# relay.net
KiCad netlist of a schematic drawn in Altium Designer
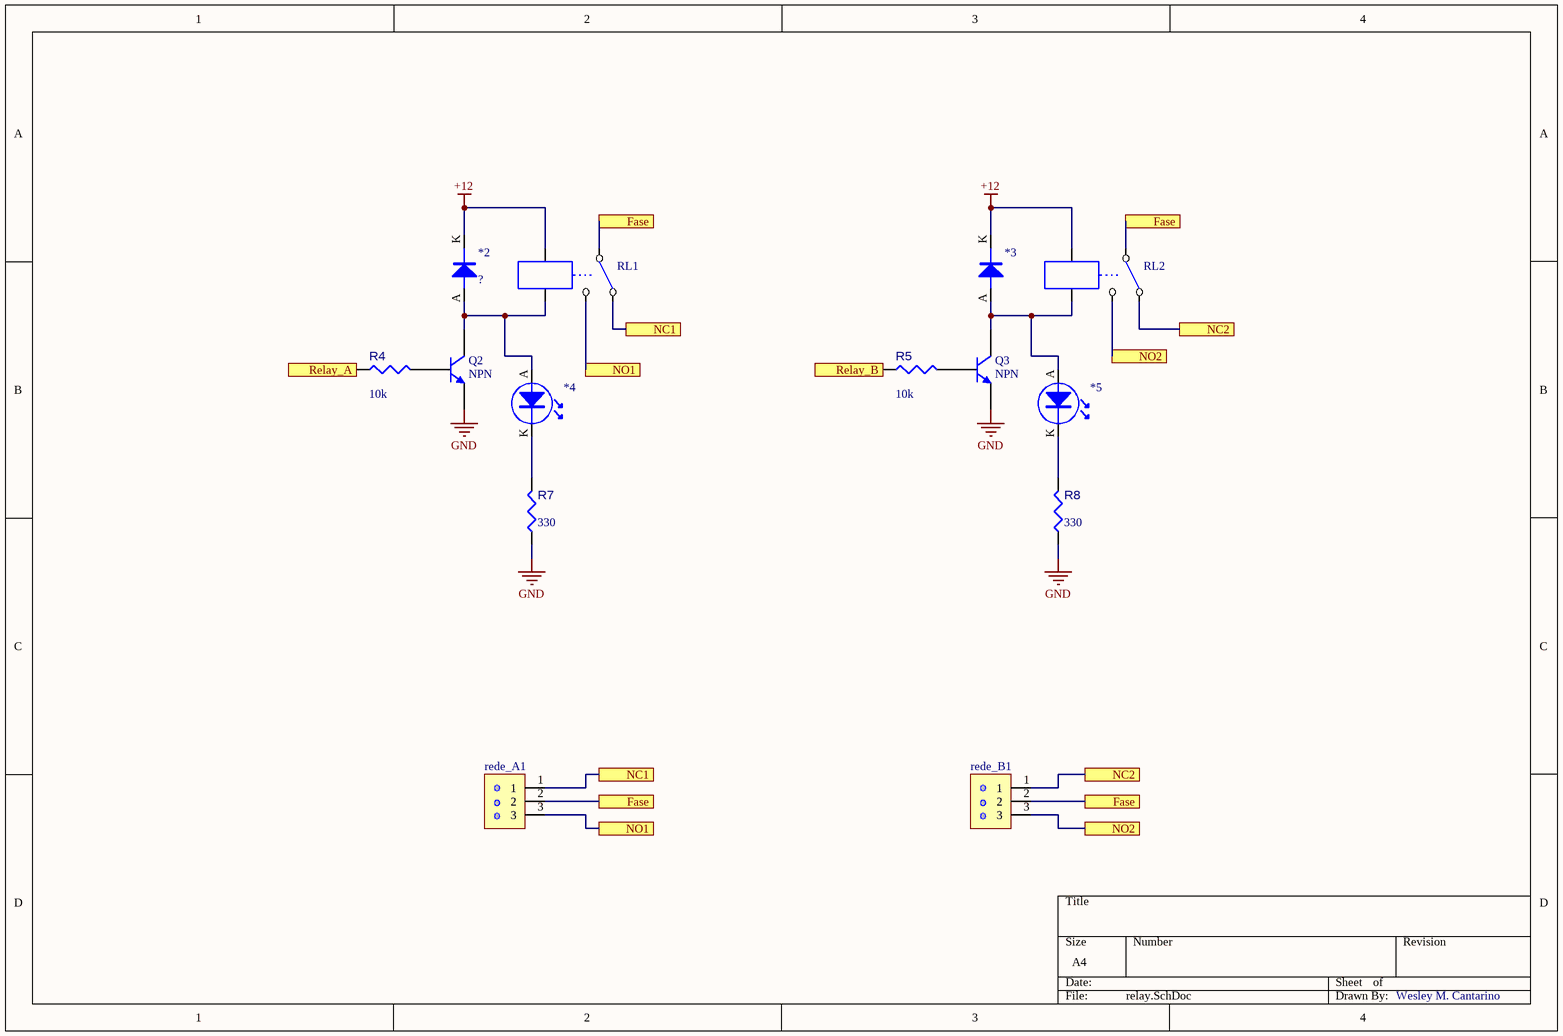
[diagram p0: relay.SchDoc]

(export (version "E")
  (design (tool "Eeschema 10.0.6"))
  (components
    (comp (ref "*2")
      (value "?")
      (footprint "DIO_PTH_DO41")
      (fields (field (name "Comment") "DIO_PTH_1N4007"))
      (libsource (lib "i9Library_Altium") (part "DIO_PTH_1N4007"))
    )
    (comp (ref "*3")
      (value "DIO_PTH_1N4007")
      (footprint "DIO_PTH_DO41")
      (libsource (lib "i9Library_Altium") (part "DIO_PTH_1N4007"))
    )
    (comp (ref "*4")
      (value "LED_AXIAL_5MM")
      (footprint "HEADER_1X2")
      (libsource (lib "i9Library_Altium") (part "LED_AXIAL_5MM"))
    )
    (comp (ref "*5")
      (value "LED_AXIAL_5MM")
      (footprint "HEADER_1X2")
      (libsource (lib "i9Library_Altium") (part "LED_AXIAL_5MM"))
    )
    (comp (ref "Q2")
      (value "NPN")
      (footprint "HEADER_1X3")
      (description "NPN Bipolar Transistor")
      (fields (field (name "PUBLISHER") "Altium Limited"))
      (libsource (lib "Miscellaneous Devices") (part "NPN"))
    )
    (comp (ref "Q3")
      (value "NPN")
      (footprint "HEADER_1X3")
      (description "NPN Bipolar Transistor")
      (fields (field (name "PUBLISHER") "Altium Limited"))
      (libsource (lib "Miscellaneous Devices") (part "NPN"))
    )
    (comp (ref "R4")
      (value "10k")
      (footprint "RES_PTH_7.62MM")
      (description "Pin Through Hole Resistor 7.62mm")
      (libsource (lib "i9Library_Altium") (part "RES_PTH_7.62MM"))
    )
    (comp (ref "R5")
      (value "10k")
      (footprint "RES_PTH_7.62MM")
      (description "Pin Through Hole Resistor 7.62mm")
      (libsource (lib "i9Library_Altium") (part "RES_PTH_7.62MM"))
    )
    (comp (ref "R7")
      (value "330")
      (footprint "RES_PTH_7.62MM")
      (description "Pin Through Hole Resistor 7.62mm")
      (libsource (lib "i9Library_Altium") (part "RES_PTH_7.62MM"))
    )
    (comp (ref "R8")
      (value "330")
      (footprint "RES_PTH_7.62MM")
      (description "Pin Through Hole Resistor 7.62mm")
      (libsource (lib "i9Library_Altium") (part "RES_PTH_7.62MM"))
    )
    (comp (ref "rede_A1")
      (value "?")
      (footprint "CN_KRE_3")
      (description "MKDS_3")
      (libsource (lib "i9Library_Altium") (part "CN_MKDS_3"))
    )
    (comp (ref "rede_B1")
      (value "?")
      (footprint "CN_KRE_3")
      (description "MKDS_3")
      (libsource (lib "i9Library_Altium") (part "CN_MKDS_3"))
    )
    (comp (ref "RL1")
      (value "RELEICR5551")
      (footprint "DIV_RELE_5551")
      (libsource (lib "i9Library_Altium") (part "RELEICR5551"))
    )
    (comp (ref "RL2")
      (value "RELEICR5551")
      (footprint "DIV_RELE_5551")
      (libsource (lib "i9Library_Altium") (part "RELEICR5551"))
    )
  )
  (nets
    (net (code "1") (name "+12") (class "Default")
      (node (ref "*2") (pin "K") (pintype "passive"))
      (node (ref "*3") (pin "K") (pintype "passive"))
      (node (ref "RL1") (pin "4") (pintype "passive"))
      (node (ref "RL2") (pin "4") (pintype "passive"))
    )
    (net (code "2") (name "/Fase") (class "Default")
      (node (ref "RL1") (pin "1") (pintype "passive"))
      (node (ref "RL2") (pin "1") (pintype "passive"))
      (node (ref "rede_A1") (pin "2") (pinfunction "2_2") (pintype "passive"))
      (node (ref "rede_B1") (pin "2") (pinfunction "2_2") (pintype "passive"))
    )
    (net (code "3") (name "/NC1") (class "Default")
      (node (ref "RL1") (pin "2") (pintype "passive"))
      (node (ref "rede_A1") (pin "1") (pinfunction "1_1") (pintype "passive"))
    )
    (net (code "4") (name "/NC2") (class "Default")
      (node (ref "RL2") (pin "2") (pintype "passive"))
      (node (ref "rede_B1") (pin "1") (pinfunction "1_1") (pintype "passive"))
    )
    (net (code "5") (name "/NO1") (class "Default")
      (node (ref "RL1") (pin "3") (pintype "passive"))
      (node (ref "rede_A1") (pin "3") (pinfunction "3_3") (pintype "passive"))
    )
    (net (code "6") (name "/NO2") (class "Default")
      (node (ref "RL2") (pin "3") (pintype "passive"))
      (node (ref "rede_B1") (pin "3") (pinfunction "3_3") (pintype "passive"))
    )
    (net (code "7") (name "/Relay_A") (class "Default")
      (node (ref "R4") (pin "1") (pinfunction "1_1") (pintype "passive"))
    )
    (net (code "8") (name "/Relay_B") (class "Default")
      (node (ref "R5") (pin "1") (pinfunction "1_1") (pintype "passive"))
    )
    (net (code "9") (name "GND") (class "Default")
      (node (ref "Q2") (pin "3") (pinfunction "E_3") (pintype "passive"))
      (node (ref "Q3") (pin "3") (pinfunction "E_3") (pintype "passive"))
      (node (ref "R7") (pin "1") (pinfunction "1_1") (pintype "passive"))
      (node (ref "R8") (pin "1") (pinfunction "1_1") (pintype "passive"))
    )
    (net (code "10") (name "Net-(*4-PadK)") (class "Default")
      (node (ref "*4") (pin "K") (pintype "passive"))
      (node (ref "R7") (pin "2") (pinfunction "2_2") (pintype "passive"))
    )
    (net (code "11") (name "Net-(*5-PadK)") (class "Default")
      (node (ref "*5") (pin "K") (pintype "passive"))
      (node (ref "R8") (pin "2") (pinfunction "2_2") (pintype "passive"))
    )
    (net (code "12") (name "Net-(Q2-B)") (class "Default")
      (node (ref "Q2") (pin "2") (pinfunction "B_2") (pintype "passive"))
      (node (ref "R4") (pin "2") (pinfunction "2_2") (pintype "passive"))
    )
    (net (code "13") (name "Net-(Q2-C)") (class "Default")
      (node (ref "*2") (pin "A") (pintype "passive"))
      (node (ref "*4") (pin "A") (pintype "passive"))
      (node (ref "Q2") (pin "1") (pinfunction "C_1") (pintype "passive"))
      (node (ref "RL1") (pin "5") (pintype "passive"))
    )
    (net (code "14") (name "Net-(Q3-B)") (class "Default")
      (node (ref "Q3") (pin "2") (pinfunction "B_2") (pintype "passive"))
      (node (ref "R5") (pin "2") (pinfunction "2_2") (pintype "passive"))
    )
    (net (code "15") (name "Net-(Q3-C)") (class "Default")
      (node (ref "*3") (pin "A") (pintype "passive"))
      (node (ref "*5") (pin "A") (pintype "passive"))
      (node (ref "Q3") (pin "1") (pinfunction "C_1") (pintype "passive"))
      (node (ref "RL2") (pin "5") (pintype "passive"))
    )
  )
)
